# eprom_reader.net
KiCad netlist of a schematic drawn in EAGLE
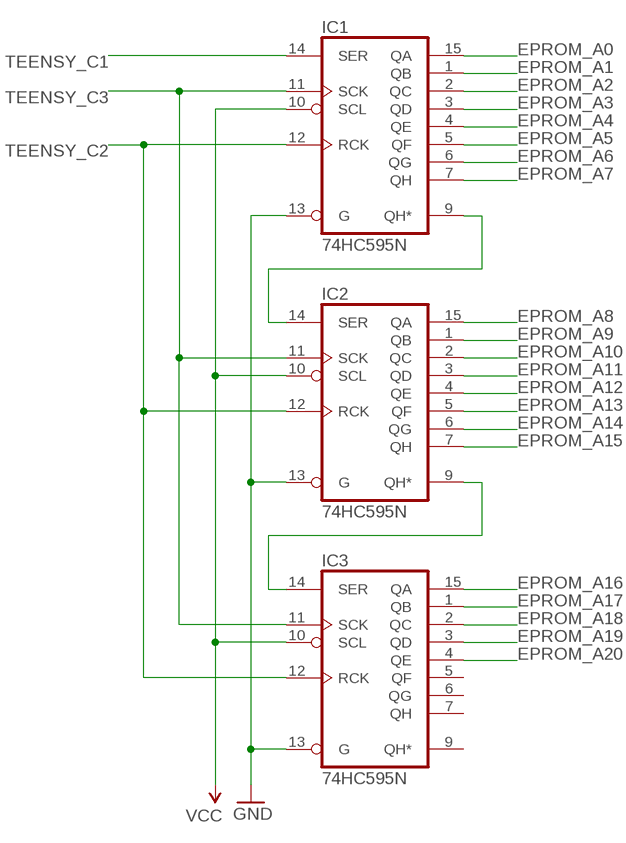
[diagram p0: schematic, sheet 1]

(export (version "E")
  (design (tool "Eeschema 10.0.6"))
  (components
    (comp (ref "IC1")
      (value "74HC595N")
      (footprint "eagle-import:DIL16")
      (libsource (lib "eagle-import") (part "74595NHC"))
    )
    (comp (ref "IC2")
      (value "74HC595N")
      (footprint "eagle-import:DIL16")
      (libsource (lib "eagle-import") (part "74595NHC"))
    )
    (comp (ref "IC3")
      (value "74HC595N")
      (footprint "eagle-import:DIL16")
      (libsource (lib "eagle-import") (part "74595NHC"))
    )
  )
  (nets
    (net (code "1") (name "/EPROM_A0") (class "Default")
      (node (ref "IC1") (pin "15") (pinfunction "QA_15") (pintype "tri_state"))
    )
    (net (code "2") (name "/EPROM_A1") (class "Default")
      (node (ref "IC1") (pin "1") (pinfunction "QB_1") (pintype "tri_state"))
    )
    (net (code "3") (name "/EPROM_A2") (class "Default")
      (node (ref "IC1") (pin "2") (pinfunction "QC_2") (pintype "tri_state"))
    )
    (net (code "4") (name "/EPROM_A3") (class "Default")
      (node (ref "IC1") (pin "3") (pinfunction "QD_3") (pintype "tri_state"))
    )
    (net (code "5") (name "/EPROM_A4") (class "Default")
      (node (ref "IC1") (pin "4") (pinfunction "QE_4") (pintype "tri_state"))
    )
    (net (code "6") (name "/EPROM_A5") (class "Default")
      (node (ref "IC1") (pin "5") (pinfunction "QF_5") (pintype "tri_state"))
    )
    (net (code "7") (name "/EPROM_A6") (class "Default")
      (node (ref "IC1") (pin "6") (pinfunction "QG_6") (pintype "tri_state"))
    )
    (net (code "8") (name "/EPROM_A7") (class "Default")
      (node (ref "IC1") (pin "7") (pinfunction "QH_7") (pintype "tri_state"))
    )
    (net (code "9") (name "/EPROM_A8") (class "Default")
      (node (ref "IC2") (pin "15") (pinfunction "QA_15") (pintype "tri_state"))
    )
    (net (code "10") (name "/EPROM_A9") (class "Default")
      (node (ref "IC2") (pin "1") (pinfunction "QB_1") (pintype "tri_state"))
    )
    (net (code "11") (name "/EPROM_A10") (class "Default")
      (node (ref "IC2") (pin "2") (pinfunction "QC_2") (pintype "tri_state"))
    )
    (net (code "12") (name "/EPROM_A11") (class "Default")
      (node (ref "IC2") (pin "3") (pinfunction "QD_3") (pintype "tri_state"))
    )
    (net (code "13") (name "/EPROM_A12") (class "Default")
      (node (ref "IC2") (pin "4") (pinfunction "QE_4") (pintype "tri_state"))
    )
    (net (code "14") (name "/EPROM_A13") (class "Default")
      (node (ref "IC2") (pin "5") (pinfunction "QF_5") (pintype "tri_state"))
    )
    (net (code "15") (name "/EPROM_A14") (class "Default")
      (node (ref "IC2") (pin "6") (pinfunction "QG_6") (pintype "tri_state"))
    )
    (net (code "16") (name "/EPROM_A15") (class "Default")
      (node (ref "IC2") (pin "7") (pinfunction "QH_7") (pintype "tri_state"))
    )
    (net (code "17") (name "/EPROM_A16") (class "Default")
      (node (ref "IC3") (pin "15") (pinfunction "QA_15") (pintype "tri_state"))
    )
    (net (code "18") (name "/EPROM_A17") (class "Default")
      (node (ref "IC3") (pin "1") (pinfunction "QB_1") (pintype "tri_state"))
    )
    (net (code "19") (name "/EPROM_A18") (class "Default")
      (node (ref "IC3") (pin "2") (pinfunction "QC_2") (pintype "tri_state"))
    )
    (net (code "20") (name "/EPROM_A19") (class "Default")
      (node (ref "IC3") (pin "3") (pinfunction "QD_3") (pintype "tri_state"))
    )
    (net (code "21") (name "/EPROM_A20") (class "Default")
      (node (ref "IC3") (pin "4") (pinfunction "QE_4") (pintype "tri_state"))
    )
    (net (code "22") (name "/TEENSY_C1") (class "Default")
      (node (ref "IC1") (pin "14") (pinfunction "SER_14") (pintype "input"))
    )
    (net (code "23") (name "/TEENSY_C2") (class "Default")
      (node (ref "IC1") (pin "12") (pinfunction "RCK_12") (pintype "input"))
      (node (ref "IC2") (pin "12") (pinfunction "RCK_12") (pintype "input"))
      (node (ref "IC3") (pin "12") (pinfunction "RCK_12") (pintype "input"))
    )
    (net (code "24") (name "/TEENSY_C3") (class "Default")
      (node (ref "IC1") (pin "11") (pinfunction "SCK_11") (pintype "input"))
      (node (ref "IC2") (pin "11") (pinfunction "SCK_11") (pintype "input"))
      (node (ref "IC3") (pin "11") (pinfunction "SCK_11") (pintype "input"))
    )
    (net (code "25") (name "GND") (class "Default")
      (node (ref "IC1") (pin "13") (pinfunction "G_13") (pintype "input"))
      (node (ref "IC2") (pin "13") (pinfunction "G_13") (pintype "input"))
      (node (ref "IC3") (pin "13") (pinfunction "G_13") (pintype "input"))
    )
    (net (code "26") (name "Net-(IC1A-QH*)") (class "Default")
      (node (ref "IC1") (pin "9") (pinfunction "QH*_9") (pintype "tri_state"))
      (node (ref "IC2") (pin "14") (pinfunction "SER_14") (pintype "input"))
    )
    (net (code "27") (name "Net-(IC2A-QH*)") (class "Default")
      (node (ref "IC2") (pin "9") (pinfunction "QH*_9") (pintype "tri_state"))
      (node (ref "IC3") (pin "14") (pinfunction "SER_14") (pintype "input"))
    )
    (net (code "28") (name "VCC") (class "Default")
      (node (ref "IC1") (pin "10") (pinfunction "SCL_10") (pintype "input"))
      (node (ref "IC2") (pin "10") (pinfunction "SCL_10") (pintype "input"))
      (node (ref "IC3") (pin "10") (pinfunction "SCL_10") (pintype "input"))
    )
    (net (code "29") (name "unconnected-(IC3A-QF-Pad5)") (class "Default")
      (node (ref "IC3") (pin "5") (pinfunction "QF_5") (pintype "tri_state"))
    )
    (net (code "30") (name "unconnected-(IC3A-QG-Pad6)") (class "Default")
      (node (ref "IC3") (pin "6") (pinfunction "QG_6") (pintype "tri_state"))
    )
    (net (code "31") (name "unconnected-(IC3A-QH*-Pad9)") (class "Default")
      (node (ref "IC3") (pin "9") (pinfunction "QH*_9") (pintype "tri_state"))
    )
    (net (code "32") (name "unconnected-(IC3A-QH-Pad7)") (class "Default")
      (node (ref "IC3") (pin "7") (pinfunction "QH_7") (pintype "tri_state"))
    )
  )
)
